# atsamdg21_v1_20.net
KiCad netlist of a schematic drawn in EAGLE
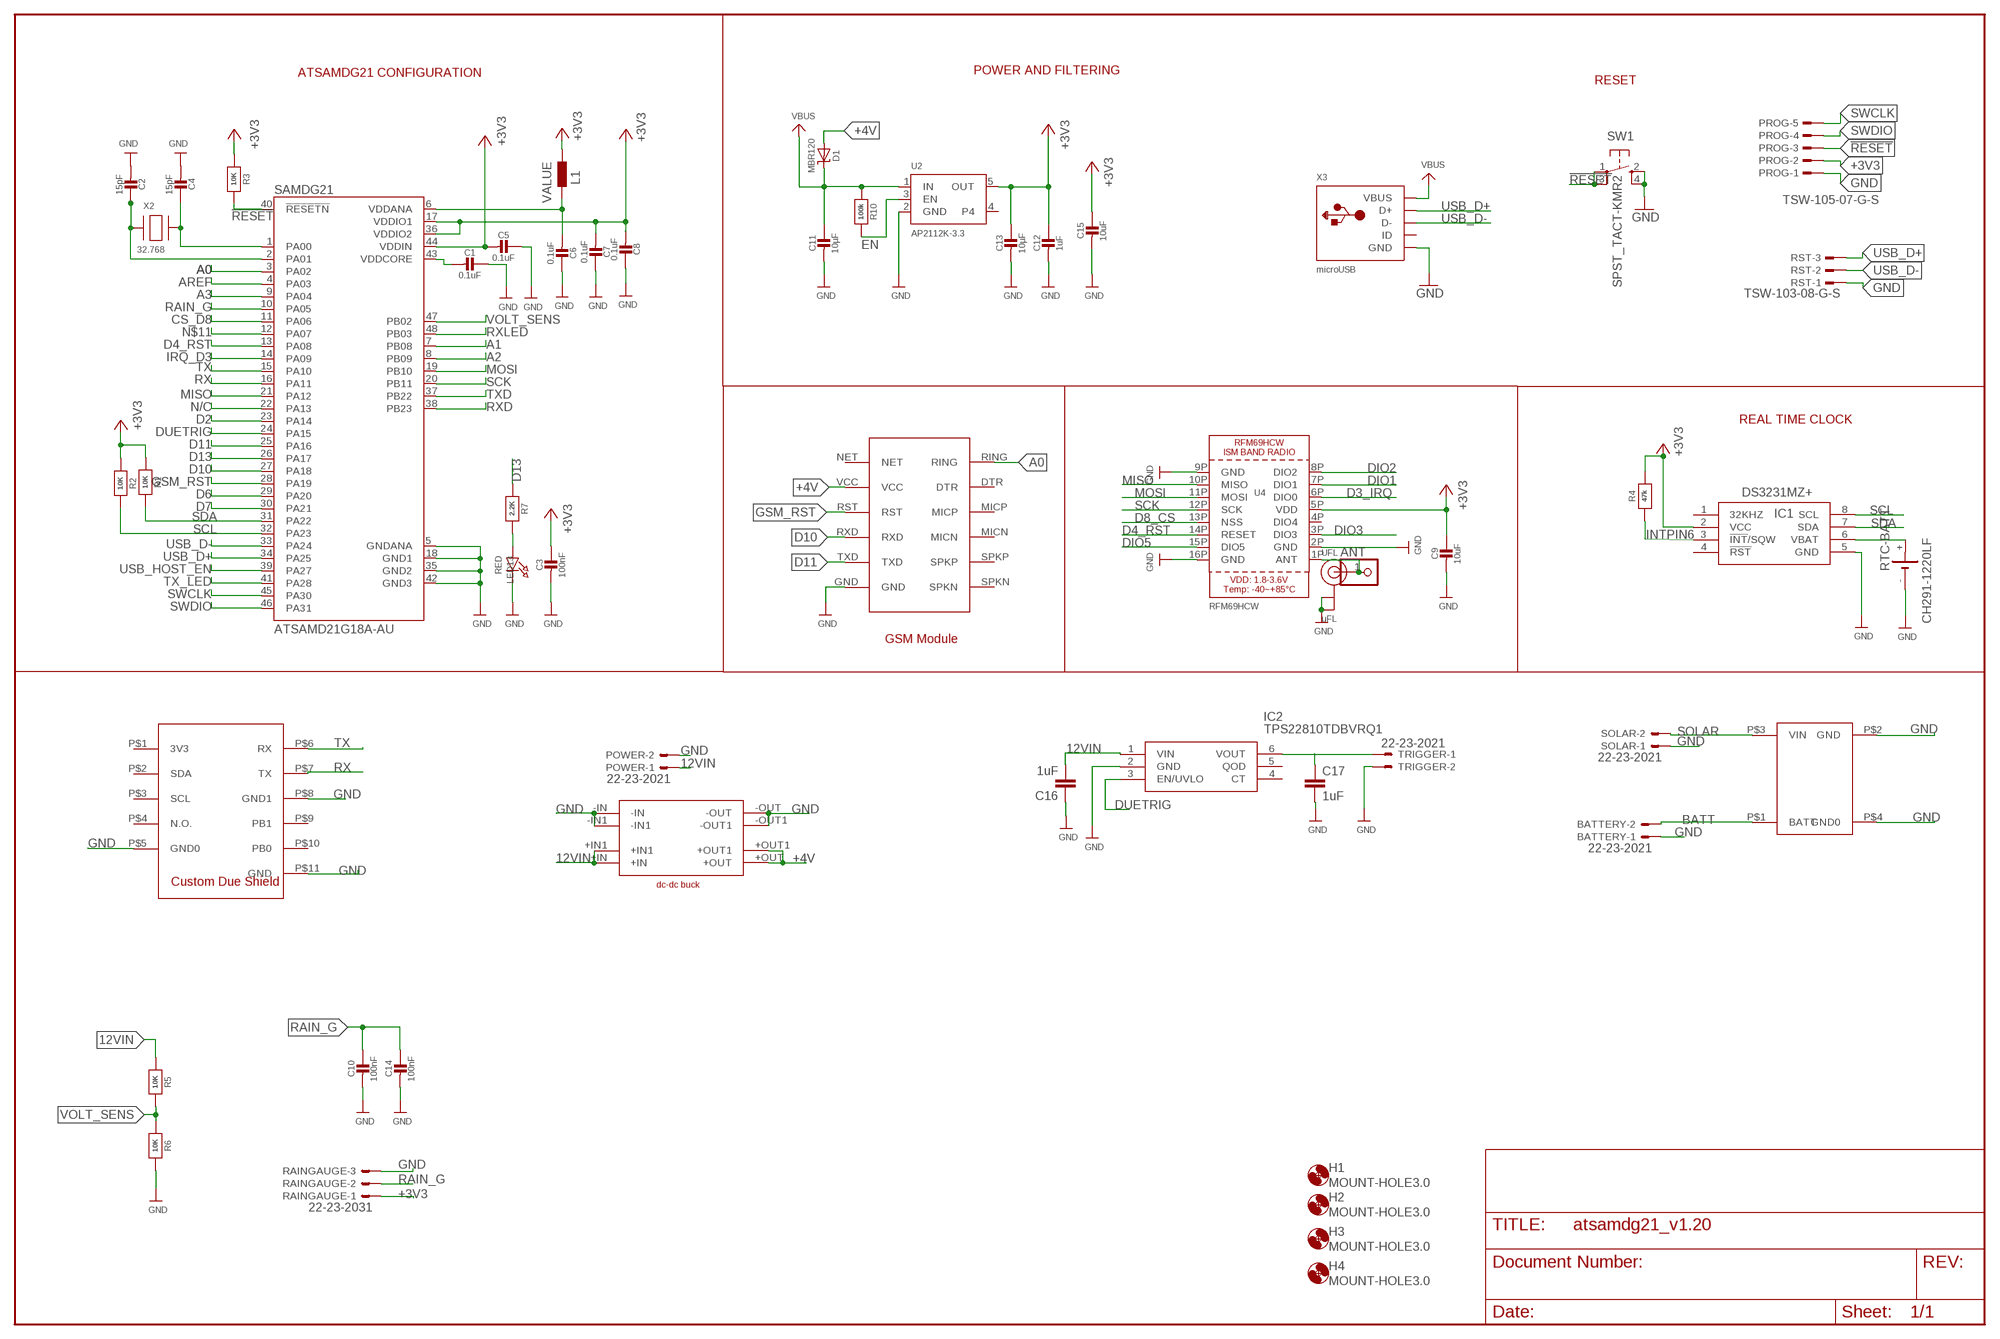
[diagram p0: schematic, sheet 1]

(export (version "E")
  (design (tool "Eeschema 10.0.6"))
  (components
    (comp (ref "ANT")
      (value "HEADER-1X1ROUND")
      (footprint "eagle-import:1X01_ROUND")
      (libsource (lib "eagle-import") (part "HEADER-1X1ROUND"))
    )
    (comp (ref "BATTERY")
      (value "22-23-2021")
      (footprint "eagle-import:22-23-2021")
      (fields (field (name "MF") "MOLEX"))
      (libsource (lib "eagle-import") (part "22-23-2021"))
    )
    (comp (ref "C1")
      (value "0.1uF")
      (footprint "eagle-import:0603-NO")
      (libsource (lib "eagle-import") (part "CAP_CERAMIC0603_NO"))
    )
    (comp (ref "C2")
      (value "15pF")
      (footprint "eagle-import:0603-NO")
      (libsource (lib "eagle-import") (part "CAP_CERAMIC0603_NO"))
    )
    (comp (ref "C3")
      (value "100nF")
      (footprint "eagle-import:0603-NO")
      (libsource (lib "eagle-import") (part "CAP_CERAMIC0603_NO"))
    )
    (comp (ref "C4")
      (value "15pF")
      (footprint "eagle-import:0603-NO")
      (libsource (lib "eagle-import") (part "CAP_CERAMIC0603_NO"))
    )
    (comp (ref "C5")
      (value "0.1uF")
      (footprint "eagle-import:0603-NO")
      (libsource (lib "eagle-import") (part "CAP_CERAMIC0603_NO"))
    )
    (comp (ref "C6")
      (value "0.1uF")
      (footprint "eagle-import:0603-NO")
      (libsource (lib "eagle-import") (part "CAP_CERAMIC0603_NO"))
    )
    (comp (ref "C7")
      (value "0.1uF")
      (footprint "eagle-import:0603-NO")
      (libsource (lib "eagle-import") (part "CAP_CERAMIC0603_NO"))
    )
    (comp (ref "C8")
      (value "0.1uF")
      (footprint "eagle-import:0603-NO")
      (libsource (lib "eagle-import") (part "CAP_CERAMIC0603_NO"))
    )
    (comp (ref "C9")
      (value "10uF")
      (footprint "eagle-import:0805-NO")
      (libsource (lib "eagle-import") (part "CAP_CERAMIC0805-NOOUTLINE"))
    )
    (comp (ref "C10")
      (value "100nF")
      (footprint "eagle-import:0603-NO")
      (libsource (lib "eagle-import") (part "CAP_CERAMIC0603_NO"))
    )
    (comp (ref "C11")
      (value "10µF")
      (footprint "eagle-import:0805-NO")
      (libsource (lib "eagle-import") (part "CAP_CERAMIC0805-NOOUTLINE"))
    )
    (comp (ref "C12")
      (value "1uF")
      (footprint "eagle-import:0603-NO")
      (libsource (lib "eagle-import") (part "CAP_CERAMIC0603_NO"))
    )
    (comp (ref "C13")
      (value "10µF")
      (footprint "eagle-import:0805-NO")
      (libsource (lib "eagle-import") (part "CAP_CERAMIC0805-NOOUTLINE"))
    )
    (comp (ref "C14")
      (value "100nF")
      (footprint "eagle-import:0603-NO")
      (libsource (lib "eagle-import") (part "CAP_CERAMIC0603_NO"))
    )
    (comp (ref "C15")
      (value "10uF")
      (footprint "eagle-import:0805-NO")
      (libsource (lib "eagle-import") (part "CAP_CERAMIC0805-NOOUTLINE"))
    )
    (comp (ref "C16")
      (value "1uF")
      (footprint "eagle-import:C0603")
      (libsource (lib "eagle-import") (part "CC0603"))
    )
    (comp (ref "C17")
      (value "1uF")
      (footprint "eagle-import:C0603")
      (libsource (lib "eagle-import") (part "CC0603"))
    )
    (comp (ref "D1")
      (value "MBR120")
      (footprint "eagle-import:SOD-123")
      (libsource (lib "eagle-import") (part "DIODE-SCHOTTKYSOD-123"))
    )
    (comp (ref "H1")
      (value "MOUNT-HOLE3.0")
      (footprint "eagle-import:3,0")
      (libsource (lib "eagle-import") (part "MOUNT-HOLE3.0"))
    )
    (comp (ref "H2")
      (value "MOUNT-HOLE3.0")
      (footprint "eagle-import:3,0")
      (libsource (lib "eagle-import") (part "MOUNT-HOLE3.0"))
    )
    (comp (ref "H3")
      (value "MOUNT-HOLE3.0")
      (footprint "eagle-import:3,0")
      (libsource (lib "eagle-import") (part "MOUNT-HOLE3.0"))
    )
    (comp (ref "H4")
      (value "MOUNT-HOLE3.0")
      (footprint "eagle-import:3,0")
      (libsource (lib "eagle-import") (part "MOUNT-HOLE3.0"))
    )
    (comp (ref "IC1")
      (value "DS3231MZ+")
      (footprint "eagle-import:SOIC127P600X175-8N")
      (fields (field (name "RS_PART_NUMBER") "1897249"))
      (libsource (lib "eagle-import") (part "DS3231MZ+"))
    )
    (comp (ref "IC2")
      (value "TPS22810TDBVRQ1")
      (footprint "eagle-import:SOT95P280X145-6N")
      (libsource (lib "eagle-import") (part "TPS22810TDBVRQ1"))
    )
    (comp (ref "L1")
      (value "BLM15HB121SN1")
      (footprint "eagle-import:0402")
      (libsource (lib "eagle-import") (part "BLM15HB121SN1"))
    )
    (comp (ref "LED13")
      (value "RED")
      (footprint "eagle-import:CHIPLED_0805_NOOUTLINE")
      (libsource (lib "eagle-import") (part "LED0805_NOOUTLINE"))
    )
    (comp (ref "POWER")
      (value "22-23-2021")
      (footprint "eagle-import:22-23-2021")
      (fields (field (name "MF") "MOLEX"))
      (libsource (lib "eagle-import") (part "22-23-2021"))
    )
    (comp (ref "PROG")
      (value "TSW-105-07-G-S")
      (footprint "eagle-import:TSW-105-XX-G-S")
      (fields (field (name "MF") "Samtec Inc."))
      (libsource (lib "eagle-import") (part "TSW-105--G-S07"))
    )
    (comp (ref "R1")
      (value "10K")
      (footprint "eagle-import:0603-NO")
      (libsource (lib "eagle-import") (part "RESISTOR_0603_NOOUT"))
    )
    (comp (ref "R2")
      (value "10K")
      (footprint "eagle-import:0603-NO")
      (libsource (lib "eagle-import") (part "RESISTOR_0603_NOOUT"))
    )
    (comp (ref "R3")
      (value "10K")
      (footprint "eagle-import:0603-NO")
      (libsource (lib "eagle-import") (part "RESISTOR_0603_NOOUT"))
    )
    (comp (ref "R4")
      (value "47k")
      (footprint "eagle-import:0603-NO")
      (libsource (lib "eagle-import") (part "RESISTOR_0603_NOOUT"))
    )
    (comp (ref "R5")
      (value "10K")
      (footprint "eagle-import:0603-NO")
      (libsource (lib "eagle-import") (part "RESISTOR_0603_NOOUT"))
    )
    (comp (ref "R6")
      (value "10K")
      (footprint "eagle-import:0603-NO")
      (libsource (lib "eagle-import") (part "RESISTOR_0603_NOOUT"))
    )
    (comp (ref "R7")
      (value "2.2K")
      (footprint "eagle-import:0603-NO")
      (libsource (lib "eagle-import") (part "RESISTOR_0603_NOOUT"))
    )
    (comp (ref "R10")
      (value "100k")
      (footprint "eagle-import:0603-NO")
      (libsource (lib "eagle-import") (part "RESISTOR_0603_NOOUT"))
    )
    (comp (ref "RAINGAUGE")
      (value "22-23-2031")
      (footprint "eagle-import:22-23-2031")
      (fields (field (name "MF") "MOLEX"))
      (libsource (lib "eagle-import") (part "22-23-2031"))
    )
    (comp (ref "RST")
      (value "TSW-103-08-G-S")
      (footprint "eagle-import:TSW-103-XX-G-S")
      (fields (field (name "MF") "Samtec Inc.") (field (name "MPN") "TSW-103-07-G-S"))
      (libsource (lib "eagle-import") (part "TSW-103--G-S08"))
    )
    (comp (ref "RTC-BATT")
      (value "CH291-1220LF")
      (footprint "eagle-import:CH291-1220LF")
      (libsource (lib "eagle-import") (part "CH291-1220LF"))
    )
    (comp (ref "SAMDG21")
      (value "ATSAMD21G18A-AU")
      (footprint "eagle-import:QFP50P900X900X120-48N")
      (fields (field (name "MF") "Microchip"))
      (libsource (lib "eagle-import") (part "ATSAMD21G18A-AU"))
    )
    (comp (ref "SOLAR")
      (value "22-23-2021")
      (footprint "eagle-import:22-23-2021")
      (fields (field (name "MF") "MOLEX"))
      (libsource (lib "eagle-import") (part "22-23-2021"))
    )
    (comp (ref "SW1")
      (value "SPST_TACT-KMR2")
      (footprint "eagle-import:KMR2")
      (libsource (lib "eagle-import") (part "SPST_TACT-KMR2"))
    )
    (comp (ref "TRIGGER")
      (value "22-23-2021")
      (footprint "eagle-import:22-23-2021")
      (fields (field (name "MF") "MOLEX"))
      (libsource (lib "eagle-import") (part "22-23-2021"))
    )
    (comp (ref "U$7")
      (value "SIM800L_MODULE")
      (footprint "eagle-import:SIM800L")
      (libsource (lib "eagle-import") (part "SIM800L_MODULE"))
    )
    (comp (ref "U$19")
      (value "DC-DC_BUCK_MAD")
      (footprint "eagle-import:DC-DC_BUCK")
      (libsource (lib "eagle-import") (part "DC-DC_BUCK_MAD"))
    )
    (comp (ref "U$20")
      (value "DUE_PADSDUE_GSM")
      (footprint "eagle-import:DUESHIELD_BIG")
      (libsource (lib "eagle-import") (part "DUE_PADSDUE_GSM"))
    )
    (comp (ref "U$36")
      (value "LI-ION-CHARGER")
      (footprint "eagle-import:LI-ION")
      (libsource (lib "eagle-import") (part "LI-ION-CHARGER"))
    )
    (comp (ref "U2")
      (value "AP2112K-3.3")
      (footprint "eagle-import:SOT23-5")
      (libsource (lib "eagle-import") (part "VREG_SOT23-5"))
    )
    (comp (ref "U4")
      (value "RFM69HCW")
      (footprint "eagle-import:RFMHCW_SMT")
      (libsource (lib "eagle-import") (part "RFM69HCW_SMT"))
    )
    (comp (ref "UFL")
      (value "uFL")
      (footprint "eagle-import:U.FL")
      (libsource (lib "eagle-import") (part "ANTENNA_U.FL"))
    )
    (comp (ref "X2")
      (value "32.768")
      (footprint "eagle-import:XTAL3215")
      (libsource (lib "eagle-import") (part "XTAL-3.2X1.5"))
    )
    (comp (ref "X3")
      (value "microUSB")
      (footprint "eagle-import:4UCONN_20329_V2")
      (libsource (lib "eagle-import") (part "USB_MICRO_20329_V2"))
    )
  )
  (nets
    (net (code "1") (name "+3V3") (class "Default")
      (node (ref "C12") (pin "1") (pinfunction "1_1") (pintype "passive"))
      (node (ref "C13") (pin "1") (pinfunction "1_1") (pintype "passive"))
      (node (ref "C15") (pin "1") (pinfunction "1_1") (pintype "passive"))
      (node (ref "C3") (pin "1") (pinfunction "1_1") (pintype "passive"))
      (node (ref "C5") (pin "2") (pinfunction "2_2") (pintype "passive"))
      (node (ref "C7") (pin "2") (pinfunction "2_2") (pintype "passive"))
      (node (ref "C8") (pin "2") (pinfunction "2_2") (pintype "passive"))
      (node (ref "C9") (pin "1") (pinfunction "1_1") (pintype "passive"))
      (node (ref "IC1") (pin "2") (pinfunction "VCC_2") (pintype "power_in"))
      (node (ref "L1") (pin "1") (pinfunction "1_1") (pintype "passive"))
      (node (ref "PROG") (pin "2") (pinfunction "1_2") (pintype "passive"))
      (node (ref "R1") (pin "1") (pinfunction "1_1") (pintype "passive"))
      (node (ref "R2") (pin "1") (pinfunction "1_1") (pintype "passive"))
      (node (ref "R3") (pin "1") (pinfunction "1_1") (pintype "passive"))
      (node (ref "R4") (pin "2") (pinfunction "2_2") (pintype "passive"))
      (node (ref "RAINGAUGE") (pin "1") (pinfunction "S_1") (pintype "passive"))
      (node (ref "SAMDG21") (pin "17") (pinfunction "VDDIO1_17") (pintype "power_in"))
      (node (ref "SAMDG21") (pin "36") (pinfunction "VDDIO2_36") (pintype "power_in"))
      (node (ref "SAMDG21") (pin "44") (pinfunction "VDDIN_44") (pintype "power_in"))
      (node (ref "U2") (pin "5") (pinfunction "OUT_5") (pintype "power_in"))
      (node (ref "U4") (pin "5P") (pinfunction "VDD_5P") (pintype "power_in"))
    )
    (net (code "2") (name "+4V") (class "Default")
      (node (ref "D1") (pin "A") (pinfunction "A_A") (pintype "passive"))
      (node (ref "U$19") (pin "+OUT") (pinfunction "+OUT_+OUT") (pintype "bidirectional"))
      (node (ref "U$19") (pin "+OUT1") (pinfunction "+OUT1_+OUT1") (pintype "bidirectional"))
      (node (ref "U$7") (pin "VCC") (pinfunction "VCC_VCC") (pintype "bidirectional"))
    )
    (net (code "3") (name "/A1") (class "Default")
      (node (ref "SAMDG21") (pin "7") (pinfunction "PB08_7") (pintype "bidirectional"))
    )
    (net (code "4") (name "/A2") (class "Default")
      (node (ref "SAMDG21") (pin "8") (pinfunction "PB09_8") (pintype "bidirectional"))
    )
    (net (code "5") (name "/A3") (class "Default")
      (node (ref "SAMDG21") (pin "9") (pinfunction "PA04_9") (pintype "bidirectional"))
    )
    (net (code "6") (name "/AREF") (class "Default")
      (node (ref "SAMDG21") (pin "4") (pinfunction "PA03_4") (pintype "bidirectional"))
    )
    (net (code "7") (name "/BATT") (class "Default")
      (node (ref "BATTERY") (pin "2") (pinfunction "S_2") (pintype "passive"))
      (node (ref "U$36") (pin "P$1") (pinfunction "BATT_P$1") (pintype "bidirectional"))
    )
    (net (code "8") (name "/CS_D8") (class "Default")
      (node (ref "SAMDG21") (pin "11") (pinfunction "PA06_11") (pintype "bidirectional"))
    )
    (net (code "9") (name "/D2") (class "Default")
      (node (ref "SAMDG21") (pin "23") (pinfunction "PA14_23") (pintype "bidirectional"))
    )
    (net (code "10") (name "/D3_IRQ") (class "Default")
      (node (ref "U4") (pin "6P") (pinfunction "DIO0_6P") (pintype "bidirectional"))
    )
    (net (code "11") (name "/D4_RST") (class "Default")
      (node (ref "SAMDG21") (pin "13") (pinfunction "PA08_13") (pintype "bidirectional"))
      (node (ref "U4") (pin "14P") (pinfunction "RESET_14P") (pintype "input"))
    )
    (net (code "12") (name "/D6") (class "Default")
      (node (ref "SAMDG21") (pin "29") (pinfunction "PA20_29") (pintype "bidirectional"))
    )
    (net (code "13") (name "/D7") (class "Default")
      (node (ref "SAMDG21") (pin "30") (pinfunction "PA21_30") (pintype "bidirectional"))
    )
    (net (code "14") (name "/D8_CS") (class "Default")
      (node (ref "U4") (pin "13P") (pinfunction "NSS_13P") (pintype "input"))
    )
    (net (code "15") (name "/D13") (class "Default")
      (node (ref "R7") (pin "1") (pinfunction "1_1") (pintype "passive"))
      (node (ref "SAMDG21") (pin "26") (pinfunction "PA17_26") (pintype "bidirectional"))
    )
    (net (code "16") (name "/DIO1") (class "Default")
      (node (ref "U4") (pin "7P") (pinfunction "DIO1_7P") (pintype "bidirectional"))
    )
    (net (code "17") (name "/DIO2") (class "Default")
      (node (ref "U4") (pin "8P") (pinfunction "DIO2_8P") (pintype "bidirectional"))
    )
    (net (code "18") (name "/DIO3") (class "Default")
      (node (ref "U4") (pin "3P") (pinfunction "DIO3_3P") (pintype "bidirectional"))
    )
    (net (code "19") (name "/DIO5") (class "Default")
      (node (ref "U4") (pin "15P") (pinfunction "DIO5_15P") (pintype "bidirectional"))
    )
    (net (code "20") (name "/DUETRIG") (class "Default")
      (node (ref "IC2") (pin "3") (pinfunction "EN/UVLO_3") (pintype "bidirectional"))
      (node (ref "SAMDG21") (pin "24") (pinfunction "PA15_24") (pintype "bidirectional"))
    )
    (net (code "21") (name "/EN") (class "Default")
      (node (ref "R10") (pin "2") (pinfunction "2_2") (pintype "passive"))
      (node (ref "U2") (pin "3") (pinfunction "EN_3") (pintype "input"))
    )
    (net (code "22") (name "/INTPIN6") (class "Default")
      (node (ref "IC1") (pin "3") (pinfunction "~{INT}/SQW_3") (pintype "input"))
      (node (ref "R4") (pin "1") (pinfunction "1_1") (pintype "passive"))
    )
    (net (code "23") (name "/IRQ_D3") (class "Default")
      (node (ref "SAMDG21") (pin "14") (pinfunction "PA09_14") (pintype "bidirectional"))
    )
    (net (code "24") (name "/MISO") (class "Default")
      (node (ref "SAMDG21") (pin "21") (pinfunction "PA12_21") (pintype "bidirectional"))
      (node (ref "U4") (pin "10P") (pinfunction "MISO_10P") (pintype "output"))
    )
    (net (code "25") (name "/MOSI") (class "Default")
      (node (ref "SAMDG21") (pin "19") (pinfunction "PB10_19") (pintype "bidirectional"))
      (node (ref "U4") (pin "11P") (pinfunction "MOSI_11P") (pintype "input"))
    )
    (net (code "26") (name "/N$6") (class "Default")
      (node (ref "C17") (pin "1") (pinfunction "1_1") (pintype "passive"))
      (node (ref "IC2") (pin "6") (pinfunction "VOUT_6") (pintype "bidirectional"))
      (node (ref "TRIGGER") (pin "1") (pinfunction "S_1") (pintype "passive"))
    )
    (net (code "27") (name "/N$11") (class "Default")
      (node (ref "SAMDG21") (pin "12") (pinfunction "PA07_12") (pintype "bidirectional"))
    )
    (net (code "28") (name "/N{slash}C") (class "Default")
      (node (ref "SAMDG21") (pin "22") (pinfunction "PA13_22") (pintype "bidirectional"))
    )
    (net (code "29") (name "/RX") (class "Default")
      (node (ref "SAMDG21") (pin "16") (pinfunction "PA11_16") (pintype "bidirectional"))
      (node (ref "U$20") (pin "P$7") (pinfunction "TX_P$7") (pintype "bidirectional"))
    )
    (net (code "30") (name "/RXD") (class "Default")
      (node (ref "SAMDG21") (pin "38") (pinfunction "PB23_38") (pintype "bidirectional"))
    )
    (net (code "31") (name "/RXLED") (class "Default")
      (node (ref "SAMDG21") (pin "48") (pinfunction "PB03_48") (pintype "bidirectional"))
    )
    (net (code "32") (name "/SCK") (class "Default")
      (node (ref "SAMDG21") (pin "20") (pinfunction "PB11_20") (pintype "bidirectional"))
      (node (ref "U4") (pin "12P") (pinfunction "SCK_12P") (pintype "input"))
    )
    (net (code "33") (name "/SCL") (class "Default")
      (node (ref "IC1") (pin "8") (pinfunction "SCL_8") (pintype "bidirectional"))
      (node (ref "R2") (pin "2") (pinfunction "2_2") (pintype "passive"))
      (node (ref "SAMDG21") (pin "32") (pinfunction "PA23_32") (pintype "bidirectional"))
    )
    (net (code "34") (name "/SDA") (class "Default")
      (node (ref "IC1") (pin "7") (pinfunction "SDA_7") (pintype "bidirectional"))
      (node (ref "R1") (pin "2") (pinfunction "2_2") (pintype "passive"))
      (node (ref "SAMDG21") (pin "31") (pinfunction "PA22_31") (pintype "bidirectional"))
    )
    (net (code "35") (name "/SOLAR") (class "Default")
      (node (ref "SOLAR") (pin "2") (pinfunction "S_2") (pintype "passive"))
      (node (ref "U$36") (pin "P$3") (pinfunction "VIN_P$3") (pintype "bidirectional"))
    )
    (net (code "36") (name "/TX") (class "Default")
      (node (ref "SAMDG21") (pin "15") (pinfunction "PA10_15") (pintype "bidirectional"))
      (node (ref "U$20") (pin "P$6") (pinfunction "RX_P$6") (pintype "bidirectional"))
    )
    (net (code "37") (name "/TXD") (class "Default")
      (node (ref "SAMDG21") (pin "37") (pinfunction "PB22_37") (pintype "bidirectional"))
    )
    (net (code "38") (name "/TX_LED") (class "Default")
      (node (ref "SAMDG21") (pin "41") (pinfunction "PA28_41") (pintype "bidirectional"))
    )
    (net (code "39") (name "/USB_HOST_EN") (class "Default")
      (node (ref "SAMDG21") (pin "39") (pinfunction "PA27_39") (pintype "bidirectional"))
    )
    (net (code "40") (name "/~{RESET}") (class "Default")
      (node (ref "PROG") (pin "3") (pinfunction "1_3") (pintype "passive"))
      (node (ref "R3") (pin "2") (pinfunction "2_2") (pintype "passive"))
      (node (ref "SAMDG21") (pin "40") (pinfunction "~{RESETN}_40") (pintype "input"))
      (node (ref "SW1") (pin "1") (pinfunction "P_1") (pintype "passive"))
      (node (ref "SW1") (pin "3") (pinfunction "P1_3") (pintype "passive"))
    )
    (net (code "41") (name "12VIN") (class "Default")
      (node (ref "C16") (pin "2") (pinfunction "2_2") (pintype "passive"))
      (node (ref "IC2") (pin "1") (pinfunction "VIN_1") (pintype "bidirectional"))
      (node (ref "POWER") (pin "1") (pinfunction "S_1") (pintype "passive"))
      (node (ref "R5") (pin "1") (pinfunction "1_1") (pintype "passive"))
      (node (ref "U$19") (pin "+IN") (pinfunction "+IN_+IN") (pintype "bidirectional"))
      (node (ref "U$19") (pin "+IN1") (pinfunction "+IN1_+IN1") (pintype "bidirectional"))
    )
    (net (code "42") (name "A0") (class "Default")
      (node (ref "SAMDG21") (pin "3") (pinfunction "PA02_3") (pintype "bidirectional"))
      (node (ref "U$7") (pin "RING") (pinfunction "RING_RING") (pintype "bidirectional"))
    )
    (net (code "43") (name "D10") (class "Default")
      (node (ref "SAMDG21") (pin "27") (pinfunction "PA18_27") (pintype "bidirectional"))
      (node (ref "U$7") (pin "RXD") (pinfunction "RXD_RXD") (pintype "bidirectional"))
    )
    (net (code "44") (name "D11") (class "Default")
      (node (ref "SAMDG21") (pin "25") (pinfunction "PA16_25") (pintype "bidirectional"))
      (node (ref "U$7") (pin "TXD") (pinfunction "TXD_TXD") (pintype "bidirectional"))
    )
    (net (code "45") (name "GND") (class "Default")
      (node (ref "BATTERY") (pin "1") (pinfunction "S_1") (pintype "passive"))
      (node (ref "C1") (pin "1") (pinfunction "1_1") (pintype "passive"))
      (node (ref "C10") (pin "2") (pinfunction "2_2") (pintype "passive"))
      (node (ref "C11") (pin "2") (pinfunction "2_2") (pintype "passive"))
      (node (ref "C12") (pin "2") (pinfunction "2_2") (pintype "passive"))
      (node (ref "C13") (pin "2") (pinfunction "2_2") (pintype "passive"))
      (node (ref "C14") (pin "2") (pinfunction "2_2") (pintype "passive"))
      (node (ref "C15") (pin "2") (pinfunction "2_2") (pintype "passive"))
      (node (ref "C16") (pin "1") (pinfunction "1_1") (pintype "passive"))
      (node (ref "C17") (pin "2") (pinfunction "2_2") (pintype "passive"))
      (node (ref "C2") (pin "2") (pinfunction "2_2") (pintype "passive"))
      (node (ref "C3") (pin "2") (pinfunction "2_2") (pintype "passive"))
      (node (ref "C4") (pin "2") (pinfunction "2_2") (pintype "passive"))
      (node (ref "C5") (pin "1") (pinfunction "1_1") (pintype "passive"))
      (node (ref "C6") (pin "1") (pinfunction "1_1") (pintype "passive"))
      (node (ref "C7") (pin "1") (pinfunction "1_1") (pintype "passive"))
      (node (ref "C8") (pin "1") (pinfunction "1_1") (pintype "passive"))
      (node (ref "C9") (pin "2") (pinfunction "2_2") (pintype "passive"))
      (node (ref "IC1") (pin "5") (pinfunction "GND_5") (pintype "power_in"))
      (node (ref "IC2") (pin "2") (pinfunction "GND_2") (pintype "bidirectional"))
      (node (ref "LED13") (pin "C") (pinfunction "C_C") (pintype "passive"))
      (node (ref "POWER") (pin "2") (pinfunction "S_2") (pintype "passive"))
      (node (ref "PROG") (pin "1") (pinfunction "1_1") (pintype "passive"))
      (node (ref "R6") (pin "2") (pinfunction "2_2") (pintype "passive"))
      (node (ref "RAINGAUGE") (pin "3") (pinfunction "S_3") (pintype "passive"))
      (node (ref "RST") (pin "1") (pinfunction "1_1") (pintype "passive"))
      (node (ref "RTC-BATT") (pin "-") (pinfunction "-_-") (pintype "passive"))
      (node (ref "SAMDG21") (pin "18") (pinfunction "GND1_18") (pintype "power_in"))
      (node (ref "SAMDG21") (pin "35") (pinfunction "GND2_35") (pintype "power_in"))
      (node (ref "SAMDG21") (pin "42") (pinfunction "GND3_42") (pintype "power_in"))
      (node (ref "SAMDG21") (pin "5") (pinfunction "GNDANA_5") (pintype "power_in"))
      (node (ref "SOLAR") (pin "1") (pinfunction "S_1") (pintype "passive"))
      (node (ref "SW1") (pin "2") (pinfunction "S_2") (pintype "passive"))
      (node (ref "SW1") (pin "4") (pinfunction "S1_4") (pintype "passive"))
      (node (ref "TRIGGER") (pin "2") (pinfunction "S_2") (pintype "passive"))
      (node (ref "U$19") (pin "-IN") (pinfunction "-IN_-IN") (pintype "bidirectional"))
      (node (ref "U$19") (pin "-IN1") (pinfunction "-IN1_-IN1") (pintype "bidirectional"))
      (node (ref "U$19") (pin "-OUT") (pinfunction "-OUT_-OUT") (pintype "bidirectional"))
      (node (ref "U$19") (pin "-OUT1") (pinfunction "-OUT1_-OUT1") (pintype "bidirectional"))
      (node (ref "U$20") (pin "P$11") (pinfunction "GND_P$11") (pintype "bidirectional"))
      (node (ref "U$20") (pin "P$5") (pinfunction "GND0_P$5") (pintype "bidirectional"))
      (node (ref "U$20") (pin "P$8") (pinfunction "GND1_P$8") (pintype "bidirectional"))
      (node (ref "U$36") (pin "P$2") (pinfunction "GND_P$2") (pintype "bidirectional"))
      (node (ref "U$36") (pin "P$4") (pinfunction "GND0_P$4") (pintype "bidirectional"))
      (node (ref "U$7") (pin "GND") (pinfunction "GND_GND") (pintype "bidirectional"))
      (node (ref "U2") (pin "2") (pinfunction "GND_2") (pintype "power_in"))
      (node (ref "U4") (pin "16P") (pinfunction "GND_16P") (pintype "power_in"))
      (node (ref "U4") (pin "2P") (pinfunction "GND_2P") (pintype "power_in"))
      (node (ref "U4") (pin "9P") (pinfunction "GND_9P") (pintype "power_in"))
      (node (ref "UFL") (pin "1") (pinfunction "GND_1") (pintype "passive"))
      (node (ref "UFL") (pin "2") (pinfunction "GND_2") (pintype "passive"))
      (node (ref "X3") (pin "BASE@1") (pinfunction "GND_BASE@1") (pintype "power_in"))
      (node (ref "X3") (pin "BASE@2") (pinfunction "GND_BASE@2") (pintype "power_in"))
      (node (ref "X3") (pin "GND") (pinfunction "GND_GND") (pintype "power_in"))
      (node (ref "X3") (pin "SPRT@1") (pinfunction "GND_SPRT@1") (pintype "power_in"))
      (node (ref "X3") (pin "SPRT@2") (pinfunction "GND_SPRT@2") (pintype "power_in"))
      (node (ref "X3") (pin "SPRT@3") (pinfunction "GND_SPRT@3") (pintype "power_in"))
      (node (ref "X3") (pin "SPRT@4") (pinfunction "GND_SPRT@4") (pintype "power_in"))
    )
    (net (code "46") (name "GSM_RST") (class "Default")
      (node (ref "SAMDG21") (pin "28") (pinfunction "PA19_28") (pintype "bidirectional"))
      (node (ref "U$7") (pin "RST") (pinfunction "RST_RST") (pintype "bidirectional"))
    )
    (net (code "47") (name "Net-(IC1-VBAT)") (class "Default")
      (node (ref "IC1") (pin "6") (pinfunction "VBAT_6") (pintype "bidirectional"))
      (node (ref "RTC-BATT") (pin "+") (pinfunction "+_+") (pintype "passive"))
    )
    (net (code "48") (name "Net-(LED13-PadA)") (class "Default")
      (node (ref "LED13") (pin "A") (pinfunction "A_A") (pintype "passive"))
      (node (ref "R7") (pin "2") (pinfunction "2_2") (pintype "passive"))
    )
    (net (code "49") (name "Net-(SAMDG21-PA00)") (class "Default")
      (node (ref "C4") (pin "1") (pinfunction "1_1") (pintype "passive"))
      (node (ref "SAMDG21") (pin "1") (pinfunction "PA00_1") (pintype "bidirectional"))
      (node (ref "X2") (pin "P$2") (pinfunction "P$2_P$2") (pintype "bidirectional"))
    )
    (net (code "50") (name "Net-(SAMDG21-PA01)") (class "Default")
      (node (ref "C2") (pin "1") (pinfunction "1_1") (pintype "passive"))
      (node (ref "SAMDG21") (pin "2") (pinfunction "PA01_2") (pintype "bidirectional"))
      (node (ref "X2") (pin "P$1") (pinfunction "P$1_P$1") (pintype "bidirectional"))
    )
    (net (code "51") (name "Net-(SAMDG21-VDDANA)") (class "Default")
      (node (ref "C6") (pin "2") (pinfunction "2_2") (pintype "passive"))
      (node (ref "L1") (pin "2") (pinfunction "2_2") (pintype "passive"))
      (node (ref "SAMDG21") (pin "6") (pinfunction "VDDANA_6") (pintype "power_in"))
    )
    (net (code "52") (name "Net-(SAMDG21-VDDCORE)") (class "Default")
      (node (ref "C1") (pin "2") (pinfunction "2_2") (pintype "passive"))
      (node (ref "SAMDG21") (pin "43") (pinfunction "VDDCORE_43") (pintype "power_in"))
    )
    (net (code "53") (name "Net-(U4-ANT)") (class "Default")
      (node (ref "ANT") (pin "1") (pinfunction "1_1") (pintype "passive"))
      (node (ref "U4") (pin "1P") (pinfunction "ANT_1P") (pintype "bidirectional"))
      (node (ref "UFL") (pin "3") (pinfunction "SIGNAL_3") (pintype "passive"))
    )
    (net (code "54") (name "RAIN_G") (class "Default")
      (node (ref "C10") (pin "1") (pinfunction "1_1") (pintype "passive"))
      (node (ref "C14") (pin "1") (pinfunction "1_1") (pintype "passive"))
      (node (ref "RAINGAUGE") (pin "2") (pinfunction "S_2") (pintype "passive"))
      (node (ref "SAMDG21") (pin "10") (pinfunction "PA05_10") (pintype "bidirectional"))
    )
    (net (code "55") (name "SWCLK") (class "Default")
      (node (ref "PROG") (pin "5") (pinfunction "1_5") (pintype "passive"))
      (node (ref "SAMDG21") (pin "45") (pinfunction "PA30_45") (pintype "bidirectional"))
    )
    (net (code "56") (name "SWDIO") (class "Default")
      (node (ref "PROG") (pin "4") (pinfunction "1_4") (pintype "passive"))
      (node (ref "SAMDG21") (pin "46") (pinfunction "PA31_46") (pintype "bidirectional"))
    )
    (net (code "57") (name "USB_D+") (class "Default")
      (node (ref "RST") (pin "3") (pinfunction "1_3") (pintype "passive"))
      (node (ref "SAMDG21") (pin "34") (pinfunction "PA25_34") (pintype "bidirectional"))
      (node (ref "X3") (pin "D+") (pinfunction "D+_D+") (pintype "bidirectional"))
    )
    (net (code "58") (name "USB_D-") (class "Default")
      (node (ref "RST") (pin "2") (pinfunction "1_2") (pintype "passive"))
      (node (ref "SAMDG21") (pin "33") (pinfunction "PA24_33") (pintype "bidirectional"))
      (node (ref "X3") (pin "D-") (pinfunction "D-_D-") (pintype "bidirectional"))
    )
    (net (code "59") (name "VBUS") (class "Default")
      (node (ref "C11") (pin "1") (pinfunction "1_1") (pintype "passive"))
      (node (ref "D1") (pin "C") (pinfunction "C_C") (pintype "passive"))
      (node (ref "R10") (pin "1") (pinfunction "1_1") (pintype "passive"))
      (node (ref "U2") (pin "1") (pinfunction "IN_1") (pintype "power_in"))
      (node (ref "X3") (pin "VBUS") (pinfunction "VBUS_VBUS") (pintype "power_in"))
    )
    (net (code "60") (name "VOLT_SENS") (class "Default")
      (node (ref "R5") (pin "2") (pinfunction "2_2") (pintype "passive"))
      (node (ref "R6") (pin "1") (pinfunction "1_1") (pintype "passive"))
      (node (ref "SAMDG21") (pin "47") (pinfunction "PB02_47") (pintype "bidirectional"))
    )
    (net (code "61") (name "unconnected-(IC1-32KHZ-Pad1)") (class "Default")
      (node (ref "IC1") (pin "1") (pinfunction "32KHZ_1") (pintype "bidirectional"))
    )
    (net (code "62") (name "unconnected-(IC1-~{RST}-Pad4)") (class "Default")
      (node (ref "IC1") (pin "4") (pinfunction "~{RST}_4") (pintype "input"))
    )
    (net (code "63") (name "unconnected-(IC2-CT-Pad4)") (class "Default")
      (node (ref "IC2") (pin "4") (pinfunction "CT_4") (pintype "bidirectional"))
    )
    (net (code "64") (name "unconnected-(IC2-QOD-Pad5)") (class "Default")
      (node (ref "IC2") (pin "5") (pinfunction "QOD_5") (pintype "bidirectional"))
    )
    (net (code "65") (name "unconnected-(U$7-PadDTR)") (class "Default")
      (node (ref "U$7") (pin "DTR") (pinfunction "DTR_DTR") (pintype "bidirectional"))
    )
    (net (code "66") (name "unconnected-(U$7-PadMICN)") (class "Default")
      (node (ref "U$7") (pin "MICN") (pinfunction "MICN_MICN") (pintype "bidirectional"))
    )
    (net (code "67") (name "unconnected-(U$7-PadMICP)") (class "Default")
      (node (ref "U$7") (pin "MICP") (pinfunction "MICP_MICP") (pintype "bidirectional"))
    )
    (net (code "68") (name "unconnected-(U$7-PadNET)") (class "Default")
      (node (ref "U$7") (pin "NET") (pinfunction "NET_NET") (pintype "bidirectional"))
    )
    (net (code "69") (name "unconnected-(U$7-PadSPKN)") (class "Default")
      (node (ref "U$7") (pin "SPKN") (pinfunction "SPKN_SPKN") (pintype "bidirectional"))
    )
    (net (code "70") (name "unconnected-(U$7-PadSPKP)") (class "Default")
      (node (ref "U$7") (pin "SPKP") (pinfunction "SPKP_SPKP") (pintype "bidirectional"))
    )
    (net (code "71") (name "unconnected-(U$20-3V3-PadP$1)") (class "Default")
      (node (ref "U$20") (pin "P$1") (pinfunction "3V3_P$1") (pintype "bidirectional"))
    )
    (net (code "72") (name "unconnected-(U$20-N.O.-PadP$4)") (class "Default")
      (node (ref "U$20") (pin "P$4") (pinfunction "N.O._P$4") (pintype "bidirectional"))
    )
    (net (code "73") (name "unconnected-(U$20-PB0-PadP$10)") (class "Default")
      (node (ref "U$20") (pin "P$10") (pinfunction "PB0_P$10") (pintype "bidirectional"))
    )
    (net (code "74") (name "unconnected-(U$20-PB1-PadP$9)") (class "Default")
      (node (ref "U$20") (pin "P$9") (pinfunction "PB1_P$9") (pintype "bidirectional"))
    )
    (net (code "75") (name "unconnected-(U$20-SCL-PadP$3)") (class "Default")
      (node (ref "U$20") (pin "P$3") (pinfunction "SCL_P$3") (pintype "bidirectional"))
    )
    (net (code "76") (name "unconnected-(U$20-SDA-PadP$2)") (class "Default")
      (node (ref "U$20") (pin "P$2") (pinfunction "SDA_P$2") (pintype "bidirectional"))
    )
    (net (code "77") (name "unconnected-(U2-P4-Pad4)") (class "Default")
      (node (ref "U2") (pin "4") (pinfunction "P4_4") (pintype "bidirectional"))
    )
    (net (code "78") (name "unconnected-(U4-DIO4-Pad4P)") (class "Default")
      (node (ref "U4") (pin "4P") (pinfunction "DIO4_4P") (pintype "bidirectional"))
    )
    (net (code "79") (name "unconnected-(X3-PadID)") (class "Default")
      (node (ref "X3") (pin "ID") (pinfunction "ID_ID") (pintype "bidirectional"))
    )
  )
)
